# joytester.net
KiCad netlist of a schematic drawn in EAGLE
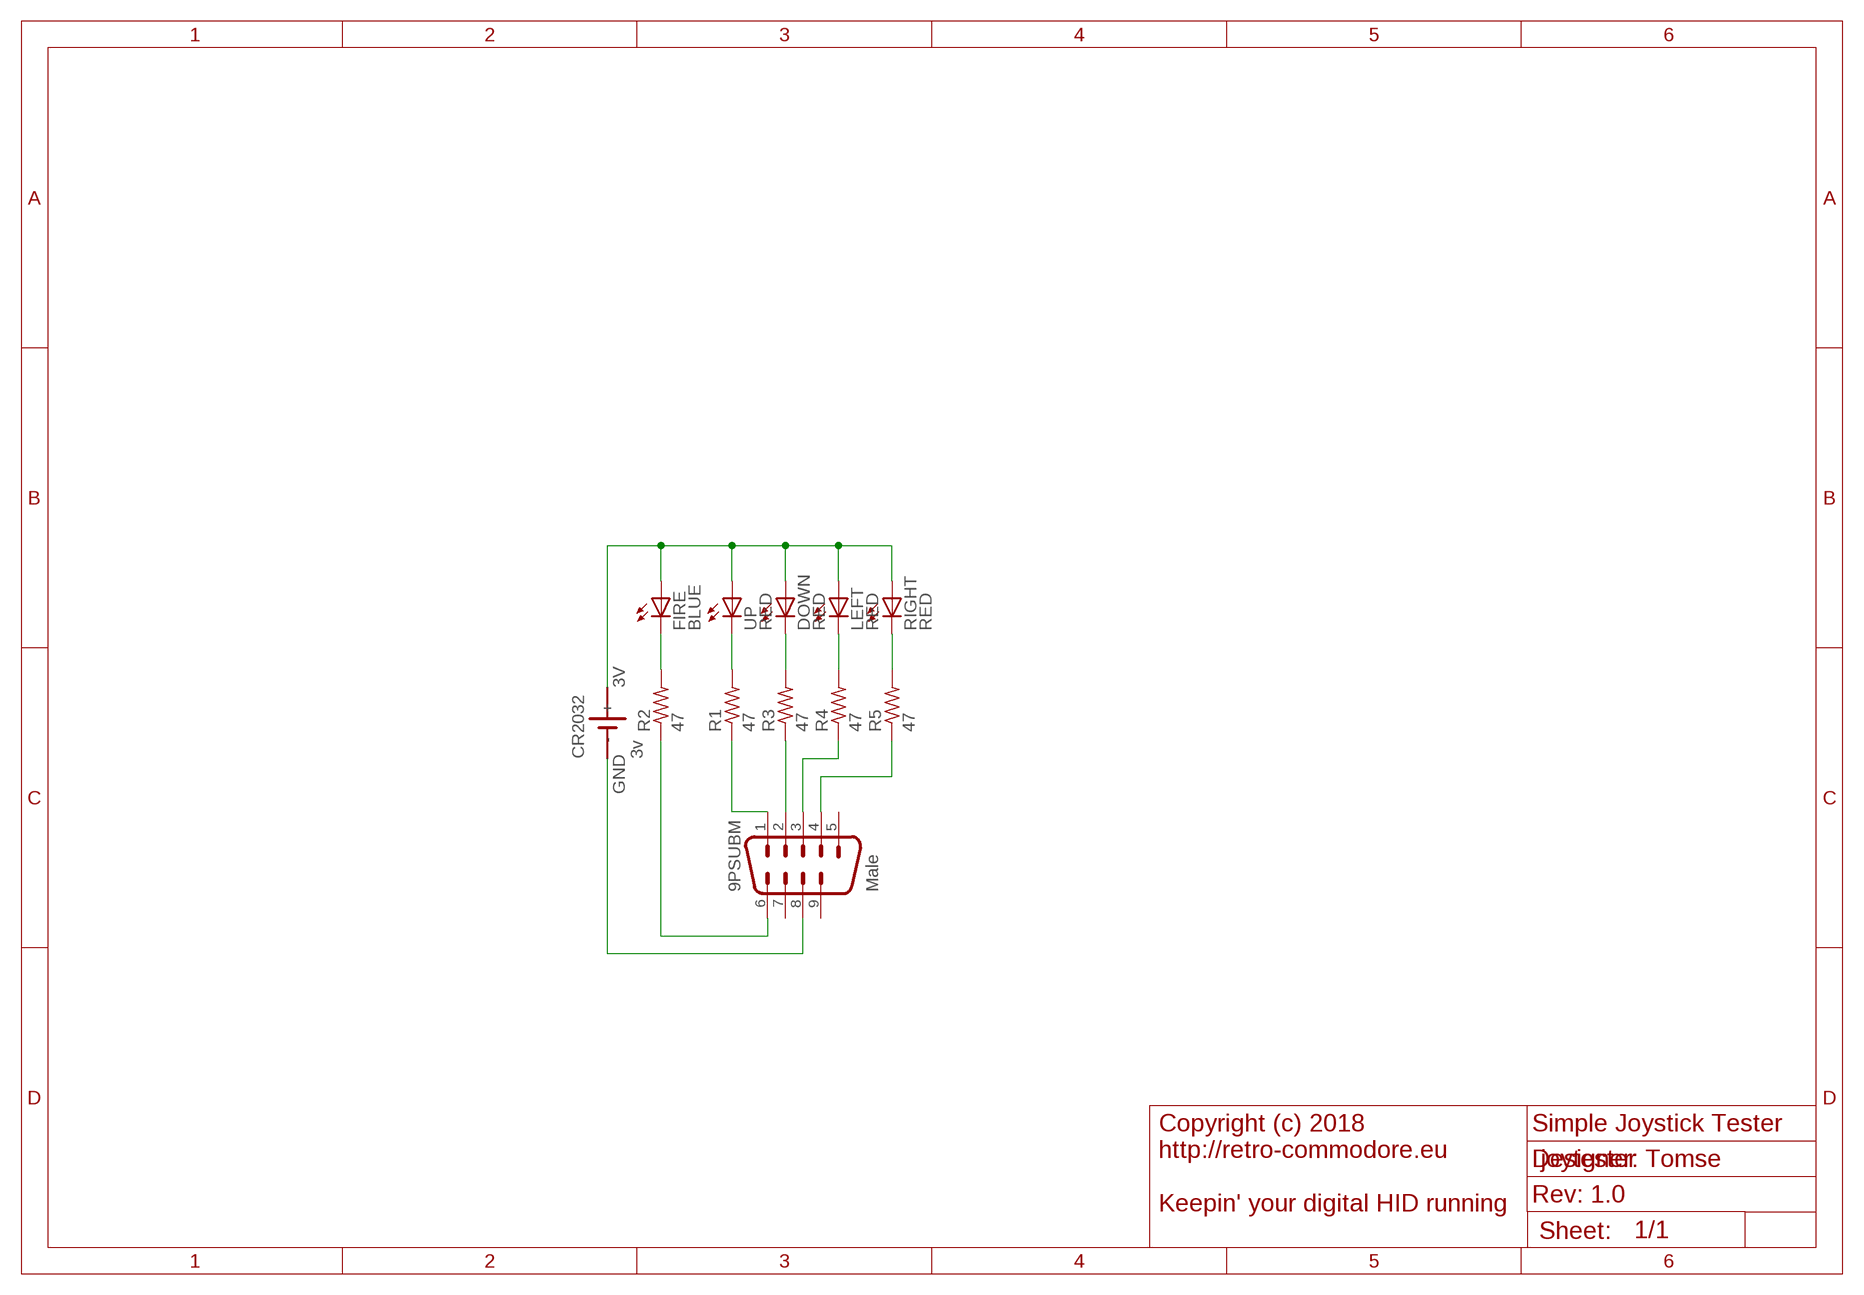
[diagram p0: schematic, sheet 1]

(export (version "E")
  (design (tool "Eeschema 10.0.6"))
  (components
    (comp (ref "9PSUBM")
      (value "Male")
      (footprint "eagle-import:M09D")
      (libsource (lib "eagle-import") (part "M09D"))
    )
    (comp (ref "CR2032")
      (value "3v")
      (footprint "eagle-import:SN2032")
      (libsource (lib "eagle-import") (part "SN2032"))
    )
    (comp (ref "DOWN")
      (value "RED")
      (footprint "eagle-import:LED5MM")
      (libsource (lib "eagle-import") (part "LED5MM"))
    )
    (comp (ref "FIRE")
      (value "BLUE")
      (footprint "eagle-import:LED5MM")
      (libsource (lib "eagle-import") (part "LED5MM"))
    )
    (comp (ref "LEFT")
      (value "RED")
      (footprint "eagle-import:LED5MM")
      (libsource (lib "eagle-import") (part "LED5MM"))
    )
    (comp (ref "R1")
      (value "47")
      (footprint "eagle-import:0207_12")
      (libsource (lib "eagle-import") (part "R-US_0207/12"))
    )
    (comp (ref "R2")
      (value "47")
      (footprint "eagle-import:0207_12")
      (libsource (lib "eagle-import") (part "R-US_0207/12"))
    )
    (comp (ref "R3")
      (value "47")
      (footprint "eagle-import:0207_12")
      (libsource (lib "eagle-import") (part "R-US_0207/12"))
    )
    (comp (ref "R4")
      (value "47")
      (footprint "eagle-import:0207_12")
      (libsource (lib "eagle-import") (part "R-US_0207/12"))
    )
    (comp (ref "R5")
      (value "47")
      (footprint "eagle-import:0207_12")
      (libsource (lib "eagle-import") (part "R-US_0207/12"))
    )
    (comp (ref "RIGHT")
      (value "RED")
      (footprint "eagle-import:LED5MM")
      (libsource (lib "eagle-import") (part "LED5MM"))
    )
    (comp (ref "UP")
      (value "RED")
      (footprint "eagle-import:LED5MM")
      (libsource (lib "eagle-import") (part "LED5MM"))
    )
  )
  (nets
    (net (code "1") (name "/3V") (class "Default")
      (node (ref "CR2032") (pin "+") (pinfunction "+_+") (pintype "passive"))
      (node (ref "DOWN") (pin "A") (pinfunction "A_A") (pintype "passive"))
      (node (ref "FIRE") (pin "A") (pinfunction "A_A") (pintype "passive"))
      (node (ref "LEFT") (pin "A") (pinfunction "A_A") (pintype "passive"))
      (node (ref "RIGHT") (pin "A") (pinfunction "A_A") (pintype "passive"))
      (node (ref "UP") (pin "A") (pinfunction "A_A") (pintype "passive"))
    )
    (net (code "2") (name "/GND") (class "Default")
      (node (ref "9PSUBM") (pin "8") (pinfunction "8_8") (pintype "passive"))
      (node (ref "CR2032") (pin "-") (pinfunction "-_-") (pintype "passive"))
    )
    (net (code "3") (name "Net-(9PSUBM-Pad1)") (class "Default")
      (node (ref "9PSUBM") (pin "1") (pinfunction "1_1") (pintype "passive"))
      (node (ref "R1") (pin "1") (pinfunction "1_1") (pintype "passive"))
    )
    (net (code "4") (name "Net-(9PSUBM-Pad2)") (class "Default")
      (node (ref "9PSUBM") (pin "2") (pinfunction "2_2") (pintype "passive"))
      (node (ref "R3") (pin "1") (pinfunction "1_1") (pintype "passive"))
    )
    (net (code "5") (name "Net-(9PSUBM-Pad3)") (class "Default")
      (node (ref "9PSUBM") (pin "3") (pinfunction "3_3") (pintype "passive"))
      (node (ref "R4") (pin "1") (pinfunction "1_1") (pintype "passive"))
    )
    (net (code "6") (name "Net-(9PSUBM-Pad4)") (class "Default")
      (node (ref "9PSUBM") (pin "4") (pinfunction "4_4") (pintype "passive"))
      (node (ref "R5") (pin "1") (pinfunction "1_1") (pintype "passive"))
    )
    (net (code "7") (name "Net-(9PSUBM-Pad6)") (class "Default")
      (node (ref "9PSUBM") (pin "6") (pinfunction "6_6") (pintype "passive"))
      (node (ref "R2") (pin "1") (pinfunction "1_1") (pintype "passive"))
    )
    (net (code "8") (name "Net-(DOWN-C)") (class "Default")
      (node (ref "DOWN") (pin "K") (pinfunction "C_K") (pintype "passive"))
      (node (ref "R3") (pin "2") (pinfunction "2_2") (pintype "passive"))
    )
    (net (code "9") (name "Net-(FIRE-C)") (class "Default")
      (node (ref "FIRE") (pin "K") (pinfunction "C_K") (pintype "passive"))
      (node (ref "R2") (pin "2") (pinfunction "2_2") (pintype "passive"))
    )
    (net (code "10") (name "Net-(LEFT-C)") (class "Default")
      (node (ref "LEFT") (pin "K") (pinfunction "C_K") (pintype "passive"))
      (node (ref "R4") (pin "2") (pinfunction "2_2") (pintype "passive"))
    )
    (net (code "11") (name "Net-(RIGHT-C)") (class "Default")
      (node (ref "R5") (pin "2") (pinfunction "2_2") (pintype "passive"))
      (node (ref "RIGHT") (pin "K") (pinfunction "C_K") (pintype "passive"))
    )
    (net (code "12") (name "Net-(UP-C)") (class "Default")
      (node (ref "R1") (pin "2") (pinfunction "2_2") (pintype "passive"))
      (node (ref "UP") (pin "K") (pinfunction "C_K") (pintype "passive"))
    )
    (net (code "13") (name "unconnected-(9PSUBM-Pad5)") (class "Default")
      (node (ref "9PSUBM") (pin "5") (pinfunction "5_5") (pintype "passive"))
    )
    (net (code "14") (name "unconnected-(9PSUBM-Pad7)") (class "Default")
      (node (ref "9PSUBM") (pin "7") (pinfunction "7_7") (pintype "passive"))
    )
    (net (code "15") (name "unconnected-(9PSUBM-Pad9)") (class "Default")
      (node (ref "9PSUBM") (pin "9") (pinfunction "9_9") (pintype "passive"))
    )
  )
)
